# USB-DA-BUF.net
KiCad netlist of a schematic drawn in EAGLE
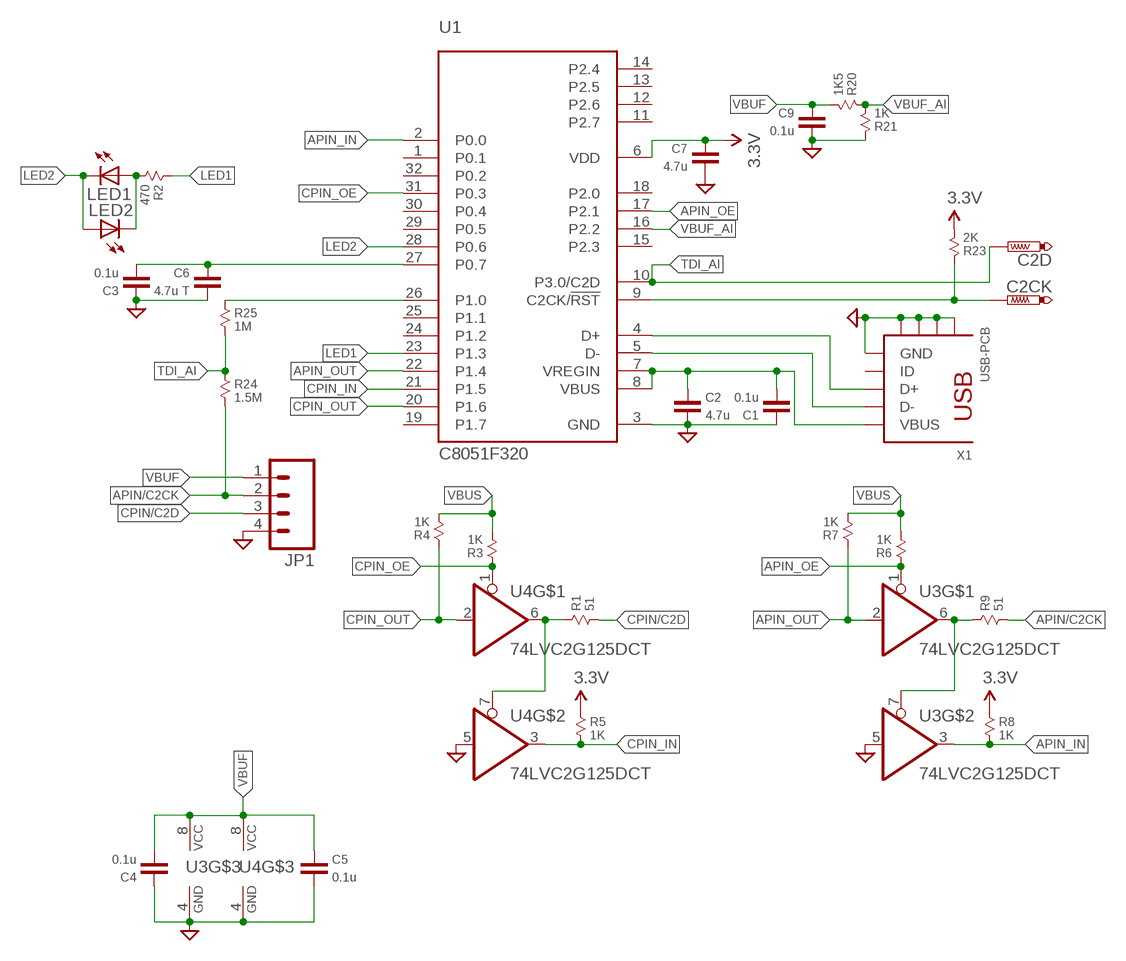
[diagram p0: schematic, sheet 1]

(export (version "E")
  (design (tool "Eeschema 10.0.6"))
  (components
    (comp (ref "C1")
      (value "0.1u")
      (footprint "eagle-import:0603")
      (libsource (lib "eagle-import") (part "CAP-0603"))
    )
    (comp (ref "C2")
      (value "4.7u")
      (footprint "eagle-import:0603")
      (libsource (lib "eagle-import") (part "CAP-0603"))
    )
    (comp (ref "C2CK")
      (value "PTR1TP10R")
      (footprint "eagle-import:TP10R")
      (libsource (lib "eagle-import") (part "PTR1TP10R"))
    )
    (comp (ref "C2D")
      (value "PTR1TP10R")
      (footprint "eagle-import:TP10R")
      (libsource (lib "eagle-import") (part "PTR1TP10R"))
    )
    (comp (ref "C3")
      (value "0.1u")
      (footprint "eagle-import:0603")
      (libsource (lib "eagle-import") (part "CAP-0603"))
    )
    (comp (ref "C4")
      (value "0.1u")
      (footprint "eagle-import:0603")
      (libsource (lib "eagle-import") (part "CAP-0603"))
    )
    (comp (ref "C5")
      (value "0.1u")
      (footprint "eagle-import:0603")
      (libsource (lib "eagle-import") (part "CAP-0603"))
    )
    (comp (ref "C6")
      (value "4.7u T")
      (footprint "eagle-import:0603")
      (libsource (lib "eagle-import") (part "CAP-0603"))
    )
    (comp (ref "C7")
      (value "4.7u")
      (footprint "eagle-import:0603")
      (libsource (lib "eagle-import") (part "CAP-0603"))
    )
    (comp (ref "C9")
      (value "0.1u")
      (footprint "eagle-import:0603")
      (libsource (lib "eagle-import") (part "CAP-0603"))
    )
    (comp (ref "JP1")
      (value "M04PTH")
      (footprint "eagle-import:1X04")
      (libsource (lib "eagle-import") (part "M04PTH"))
    )
    (comp (ref "LED1")
      (value "LED0603")
      (footprint "eagle-import:LED-0603")
      (libsource (lib "eagle-import") (part "LED0603"))
    )
    (comp (ref "LED2")
      (value "LED0603")
      (footprint "eagle-import:LED-0603")
      (libsource (lib "eagle-import") (part "LED0603"))
    )
    (comp (ref "R1")
      (value "51")
      (footprint "eagle-import:0603")
      (libsource (lib "eagle-import") (part "RESISTOR-0603"))
    )
    (comp (ref "R2")
      (value "470")
      (footprint "eagle-import:0603")
      (libsource (lib "eagle-import") (part "RESISTOR-0603"))
    )
    (comp (ref "R3")
      (value "1K")
      (footprint "eagle-import:0603")
      (libsource (lib "eagle-import") (part "RESISTOR-0603"))
    )
    (comp (ref "R4")
      (value "1K")
      (footprint "eagle-import:0603")
      (libsource (lib "eagle-import") (part "RESISTOR-0603"))
    )
    (comp (ref "R5")
      (value "1K")
      (footprint "eagle-import:0603")
      (libsource (lib "eagle-import") (part "RESISTOR-0603"))
    )
    (comp (ref "R6")
      (value "1K")
      (footprint "eagle-import:0603")
      (libsource (lib "eagle-import") (part "RESISTOR-0603"))
    )
    (comp (ref "R7")
      (value "1K")
      (footprint "eagle-import:0603")
      (libsource (lib "eagle-import") (part "RESISTOR-0603"))
    )
    (comp (ref "R8")
      (value "1K")
      (footprint "eagle-import:0603")
      (libsource (lib "eagle-import") (part "RESISTOR-0603"))
    )
    (comp (ref "R9")
      (value "51")
      (footprint "eagle-import:0603")
      (libsource (lib "eagle-import") (part "RESISTOR-0603"))
    )
    (comp (ref "R20")
      (value "1K5")
      (footprint "eagle-import:0603")
      (libsource (lib "eagle-import") (part "RESISTOR-0603"))
    )
    (comp (ref "R21")
      (value "1K")
      (footprint "eagle-import:0603")
      (libsource (lib "eagle-import") (part "RESISTOR-0603"))
    )
    (comp (ref "R23")
      (value "2K")
      (footprint "eagle-import:0603")
      (libsource (lib "eagle-import") (part "RESISTOR-0603"))
    )
    (comp (ref "R24")
      (value "1.5M")
      (footprint "eagle-import:0603")
      (libsource (lib "eagle-import") (part "RESISTOR-0603"))
    )
    (comp (ref "R25")
      (value "1M")
      (footprint "eagle-import:0603")
      (libsource (lib "eagle-import") (part "RESISTOR-0603"))
    )
    (comp (ref "U1")
      (value "C8051F320")
      (footprint "eagle-import:LQFP32")
      (libsource (lib "eagle-import") (part "C8051F320"))
    )
    (comp (ref "U3")
      (value "74LVC2G125DCT")
      (footprint "eagle-import:SSOP08")
      (libsource (lib "eagle-import") (part "742G125DCTLVC"))
    )
    (comp (ref "U4")
      (value "74LVC2G125DCT")
      (footprint "eagle-import:SSOP08")
      (libsource (lib "eagle-import") (part "742G125DCTLVC"))
    )
    (comp (ref "X1")
      (value "USB-PCB")
      (footprint "eagle-import:USB-MINIB")
      (libsource (lib "eagle-import") (part "USB-SMD"))
    )
  )
  (nets
    (net (code "1") (name "3.3V") (class "Default")
      (node (ref "C7") (pin "2") (pinfunction "2_2") (pintype "passive"))
      (node (ref "R23") (pin "2") (pinfunction "2_2") (pintype "passive"))
      (node (ref "R5") (pin "1") (pinfunction "1_1") (pintype "passive"))
      (node (ref "R8") (pin "1") (pinfunction "1_1") (pintype "passive"))
      (node (ref "U1") (pin "6") (pinfunction "VDD_6") (pintype "power_in"))
    )
    (net (code "2") (name "APIN_IN") (class "Default")
      (node (ref "R8") (pin "2") (pinfunction "2_2") (pintype "passive"))
      (node (ref "U1") (pin "2") (pinfunction "P0.0_2") (pintype "bidirectional"))
      (node (ref "U3") (pin "3") (pinfunction "O_3") (pintype "tri_state"))
    )
    (net (code "3") (name "APIN_OE") (class "Default")
      (node (ref "R6") (pin "1") (pinfunction "1_1") (pintype "passive"))
      (node (ref "U1") (pin "17") (pinfunction "P2.1_17") (pintype "bidirectional"))
      (node (ref "U3") (pin "1") (pinfunction "OE_1") (pintype "input"))
    )
    (net (code "4") (name "APIN_OUT") (class "Default")
      (node (ref "R7") (pin "1") (pinfunction "1_1") (pintype "passive"))
      (node (ref "U1") (pin "22") (pinfunction "P1.4_22") (pintype "bidirectional"))
      (node (ref "U3") (pin "2") (pinfunction "I_2") (pintype "input"))
    )
    (net (code "5") (name "APIN{slash}C2CK") (class "Default")
      (node (ref "JP1") (pin "2") (pinfunction "2_2") (pintype "passive"))
      (node (ref "R24") (pin "2") (pinfunction "2_2") (pintype "passive"))
      (node (ref "R9") (pin "2") (pinfunction "2_2") (pintype "passive"))
    )
    (net (code "6") (name "CPIN_IN") (class "Default")
      (node (ref "R5") (pin "2") (pinfunction "2_2") (pintype "passive"))
      (node (ref "U1") (pin "21") (pinfunction "P1.5_21") (pintype "bidirectional"))
      (node (ref "U4") (pin "3") (pinfunction "O_3") (pintype "tri_state"))
    )
    (net (code "7") (name "CPIN_OE") (class "Default")
      (node (ref "R3") (pin "1") (pinfunction "1_1") (pintype "passive"))
      (node (ref "U1") (pin "31") (pinfunction "P0.3_31") (pintype "bidirectional"))
      (node (ref "U4") (pin "1") (pinfunction "OE_1") (pintype "input"))
    )
    (net (code "8") (name "CPIN_OUT") (class "Default")
      (node (ref "R4") (pin "1") (pinfunction "1_1") (pintype "passive"))
      (node (ref "U1") (pin "20") (pinfunction "P1.6_20") (pintype "bidirectional"))
      (node (ref "U4") (pin "2") (pinfunction "I_2") (pintype "input"))
    )
    (net (code "9") (name "CPIN{slash}C2D") (class "Default")
      (node (ref "JP1") (pin "3") (pinfunction "3_3") (pintype "passive"))
      (node (ref "R1") (pin "2") (pinfunction "2_2") (pintype "passive"))
    )
    (net (code "10") (name "GND") (class "Default")
      (node (ref "C1") (pin "2") (pinfunction "2_2") (pintype "passive"))
      (node (ref "C2") (pin "1") (pinfunction "1_1") (pintype "passive"))
      (node (ref "C3") (pin "2") (pinfunction "2_2") (pintype "passive"))
      (node (ref "C4") (pin "2") (pinfunction "2_2") (pintype "passive"))
      (node (ref "C5") (pin "1") (pinfunction "1_1") (pintype "passive"))
      (node (ref "C6") (pin "1") (pinfunction "1_1") (pintype "passive"))
      (node (ref "C7") (pin "1") (pinfunction "1_1") (pintype "passive"))
      (node (ref "C9") (pin "1") (pinfunction "1_1") (pintype "passive"))
      (node (ref "JP1") (pin "4") (pinfunction "4_4") (pintype "passive"))
      (node (ref "R21") (pin "1") (pinfunction "1_1") (pintype "passive"))
      (node (ref "U1") (pin "3") (pinfunction "GND_3") (pintype "power_in"))
      (node (ref "U3") (pin "4") (pinfunction "GND_4") (pintype "power_in"))
      (node (ref "U3") (pin "5") (pinfunction "I_5") (pintype "input"))
      (node (ref "U4") (pin "4") (pinfunction "GND_4") (pintype "power_in"))
      (node (ref "U4") (pin "5") (pinfunction "I_5") (pintype "input"))
      (node (ref "X1") (pin "GND") (pinfunction "GND_GND") (pintype "power_in"))
      (node (ref "X1") (pin "GND@1") (pinfunction "GND_GND@1") (pintype "power_in"))
      (node (ref "X1") (pin "GND@2") (pinfunction "GND_GND@2") (pintype "power_in"))
      (node (ref "X1") (pin "GND@3") (pinfunction "GND_GND@3") (pintype "power_in"))
      (node (ref "X1") (pin "GND@4") (pinfunction "GND_GND@4") (pintype "power_in"))
    )
    (net (code "11") (name "LED1") (class "Default")
      (node (ref "R2") (pin "1") (pinfunction "1_1") (pintype "passive"))
      (node (ref "U1") (pin "23") (pinfunction "P1.3_23") (pintype "bidirectional"))
    )
    (net (code "12") (name "LED2") (class "Default")
      (node (ref "LED1") (pin "C") (pinfunction "C_C") (pintype "passive"))
      (node (ref "LED2") (pin "A") (pinfunction "A_A") (pintype "passive"))
      (node (ref "U1") (pin "28") (pinfunction "P0.6_28") (pintype "bidirectional"))
    )
    (net (code "13") (name "Net-(LED1-PadA)") (class "Default")
      (node (ref "LED1") (pin "A") (pinfunction "A_A") (pintype "passive"))
      (node (ref "LED2") (pin "C") (pinfunction "C_C") (pintype "passive"))
      (node (ref "R2") (pin "2") (pinfunction "2_2") (pintype "passive"))
    )
    (net (code "14") (name "Net-(U1-C2CK{slash}~{RST})") (class "Default")
      (node (ref "C2CK") (pin "TP") (pinfunction "TP_TP") (pintype "input"))
      (node (ref "R23") (pin "1") (pinfunction "1_1") (pintype "passive"))
      (node (ref "U1") (pin "9") (pinfunction "C2CK/~{RST}_9") (pintype "bidirectional"))
    )
    (net (code "15") (name "Net-(U1-D+)") (class "Default")
      (node (ref "U1") (pin "4") (pinfunction "D+_4") (pintype "bidirectional"))
      (node (ref "X1") (pin "D+") (pinfunction "D+_D+") (pintype "bidirectional"))
    )
    (net (code "16") (name "Net-(U1-D-)") (class "Default")
      (node (ref "U1") (pin "5") (pinfunction "D-_5") (pintype "bidirectional"))
      (node (ref "X1") (pin "D-") (pinfunction "D-_D-") (pintype "bidirectional"))
    )
    (net (code "17") (name "Net-(U1-P0.7)") (class "Default")
      (node (ref "C3") (pin "1") (pinfunction "1_1") (pintype "passive"))
      (node (ref "C6") (pin "2") (pinfunction "2_2") (pintype "passive"))
      (node (ref "U1") (pin "27") (pinfunction "P0.7_27") (pintype "bidirectional"))
    )
    (net (code "18") (name "Net-(U1-P1.0)") (class "Default")
      (node (ref "R25") (pin "1") (pinfunction "1_1") (pintype "passive"))
      (node (ref "U1") (pin "26") (pinfunction "P1.0_26") (pintype "bidirectional"))
    )
    (net (code "19") (name "Net-(U3A-O)") (class "Default")
      (node (ref "R9") (pin "1") (pinfunction "1_1") (pintype "passive"))
      (node (ref "U3") (pin "6") (pinfunction "O_6") (pintype "tri_state"))
      (node (ref "U3") (pin "7") (pinfunction "OE_7") (pintype "input"))
    )
    (net (code "20") (name "Net-(U4A-O)") (class "Default")
      (node (ref "R1") (pin "1") (pinfunction "1_1") (pintype "passive"))
      (node (ref "U4") (pin "6") (pinfunction "O_6") (pintype "tri_state"))
      (node (ref "U4") (pin "7") (pinfunction "OE_7") (pintype "input"))
    )
    (net (code "21") (name "TDI_AI") (class "Default")
      (node (ref "C2D") (pin "TP") (pinfunction "TP_TP") (pintype "input"))
      (node (ref "R24") (pin "1") (pinfunction "1_1") (pintype "passive"))
      (node (ref "R25") (pin "2") (pinfunction "2_2") (pintype "passive"))
      (node (ref "U1") (pin "10") (pinfunction "P3.0/C2D_10") (pintype "bidirectional"))
    )
    (net (code "22") (name "VBUF") (class "Default")
      (node (ref "C4") (pin "1") (pinfunction "1_1") (pintype "passive"))
      (node (ref "C5") (pin "2") (pinfunction "2_2") (pintype "passive"))
      (node (ref "C9") (pin "2") (pinfunction "2_2") (pintype "passive"))
      (node (ref "JP1") (pin "1") (pinfunction "1_1") (pintype "passive"))
      (node (ref "R20") (pin "2") (pinfunction "2_2") (pintype "passive"))
      (node (ref "U3") (pin "8") (pinfunction "VCC_8") (pintype "power_in"))
      (node (ref "U4") (pin "8") (pinfunction "VCC_8") (pintype "power_in"))
    )
    (net (code "23") (name "VBUF_AI") (class "Default")
      (node (ref "R20") (pin "1") (pinfunction "1_1") (pintype "passive"))
      (node (ref "R21") (pin "2") (pinfunction "2_2") (pintype "passive"))
      (node (ref "U1") (pin "16") (pinfunction "P2.2_16") (pintype "bidirectional"))
    )
    (net (code "24") (name "VBUS") (class "Default")
      (node (ref "C1") (pin "1") (pinfunction "1_1") (pintype "passive"))
      (node (ref "C2") (pin "2") (pinfunction "2_2") (pintype "passive"))
      (node (ref "R3") (pin "2") (pinfunction "2_2") (pintype "passive"))
      (node (ref "R4") (pin "2") (pinfunction "2_2") (pintype "passive"))
      (node (ref "R6") (pin "2") (pinfunction "2_2") (pintype "passive"))
      (node (ref "R7") (pin "2") (pinfunction "2_2") (pintype "passive"))
      (node (ref "U1") (pin "7") (pinfunction "VREGIN_7") (pintype "bidirectional"))
      (node (ref "U1") (pin "8") (pinfunction "VBUS_8") (pintype "bidirectional"))
      (node (ref "X1") (pin "VBUS") (pinfunction "VBUS_VBUS") (pintype "passive"))
    )
    (net (code "25") (name "unconnected-(U1-P0.1-Pad1)") (class "Default")
      (node (ref "U1") (pin "1") (pinfunction "P0.1_1") (pintype "bidirectional"))
    )
    (net (code "26") (name "unconnected-(U1-P0.2-Pad32)") (class "Default")
      (node (ref "U1") (pin "32") (pinfunction "P0.2_32") (pintype "bidirectional"))
    )
    (net (code "27") (name "unconnected-(U1-P0.4-Pad30)") (class "Default")
      (node (ref "U1") (pin "30") (pinfunction "P0.4_30") (pintype "bidirectional"))
    )
    (net (code "28") (name "unconnected-(U1-P0.5-Pad29)") (class "Default")
      (node (ref "U1") (pin "29") (pinfunction "P0.5_29") (pintype "bidirectional"))
    )
    (net (code "29") (name "unconnected-(U1-P1.1-Pad25)") (class "Default")
      (node (ref "U1") (pin "25") (pinfunction "P1.1_25") (pintype "bidirectional"))
    )
    (net (code "30") (name "unconnected-(U1-P1.2-Pad24)") (class "Default")
      (node (ref "U1") (pin "24") (pinfunction "P1.2_24") (pintype "bidirectional"))
    )
    (net (code "31") (name "unconnected-(U1-P1.7-Pad19)") (class "Default")
      (node (ref "U1") (pin "19") (pinfunction "P1.7_19") (pintype "bidirectional"))
    )
    (net (code "32") (name "unconnected-(U1-P2.0-Pad18)") (class "Default")
      (node (ref "U1") (pin "18") (pinfunction "P2.0_18") (pintype "bidirectional"))
    )
    (net (code "33") (name "unconnected-(U1-P2.3-Pad15)") (class "Default")
      (node (ref "U1") (pin "15") (pinfunction "P2.3_15") (pintype "bidirectional"))
    )
    (net (code "34") (name "unconnected-(U1-P2.4-Pad14)") (class "Default")
      (node (ref "U1") (pin "14") (pinfunction "P2.4_14") (pintype "bidirectional"))
    )
    (net (code "35") (name "unconnected-(U1-P2.5-Pad13)") (class "Default")
      (node (ref "U1") (pin "13") (pinfunction "P2.5_13") (pintype "bidirectional"))
    )
    (net (code "36") (name "unconnected-(U1-P2.6-Pad12)") (class "Default")
      (node (ref "U1") (pin "12") (pinfunction "P2.6_12") (pintype "bidirectional"))
    )
    (net (code "37") (name "unconnected-(U1-P2.7-Pad11)") (class "Default")
      (node (ref "U1") (pin "11") (pinfunction "P2.7_11") (pintype "bidirectional"))
    )
    (net (code "38") (name "unconnected-(X1-PadID)") (class "Default")
      (node (ref "X1") (pin "ID") (pinfunction "ID_ID") (pintype "bidirectional"))
    )
  )
)
